# TPS54560_5V_optymalizacja.net
KiCad netlist of a schematic drawn in Altium Designer
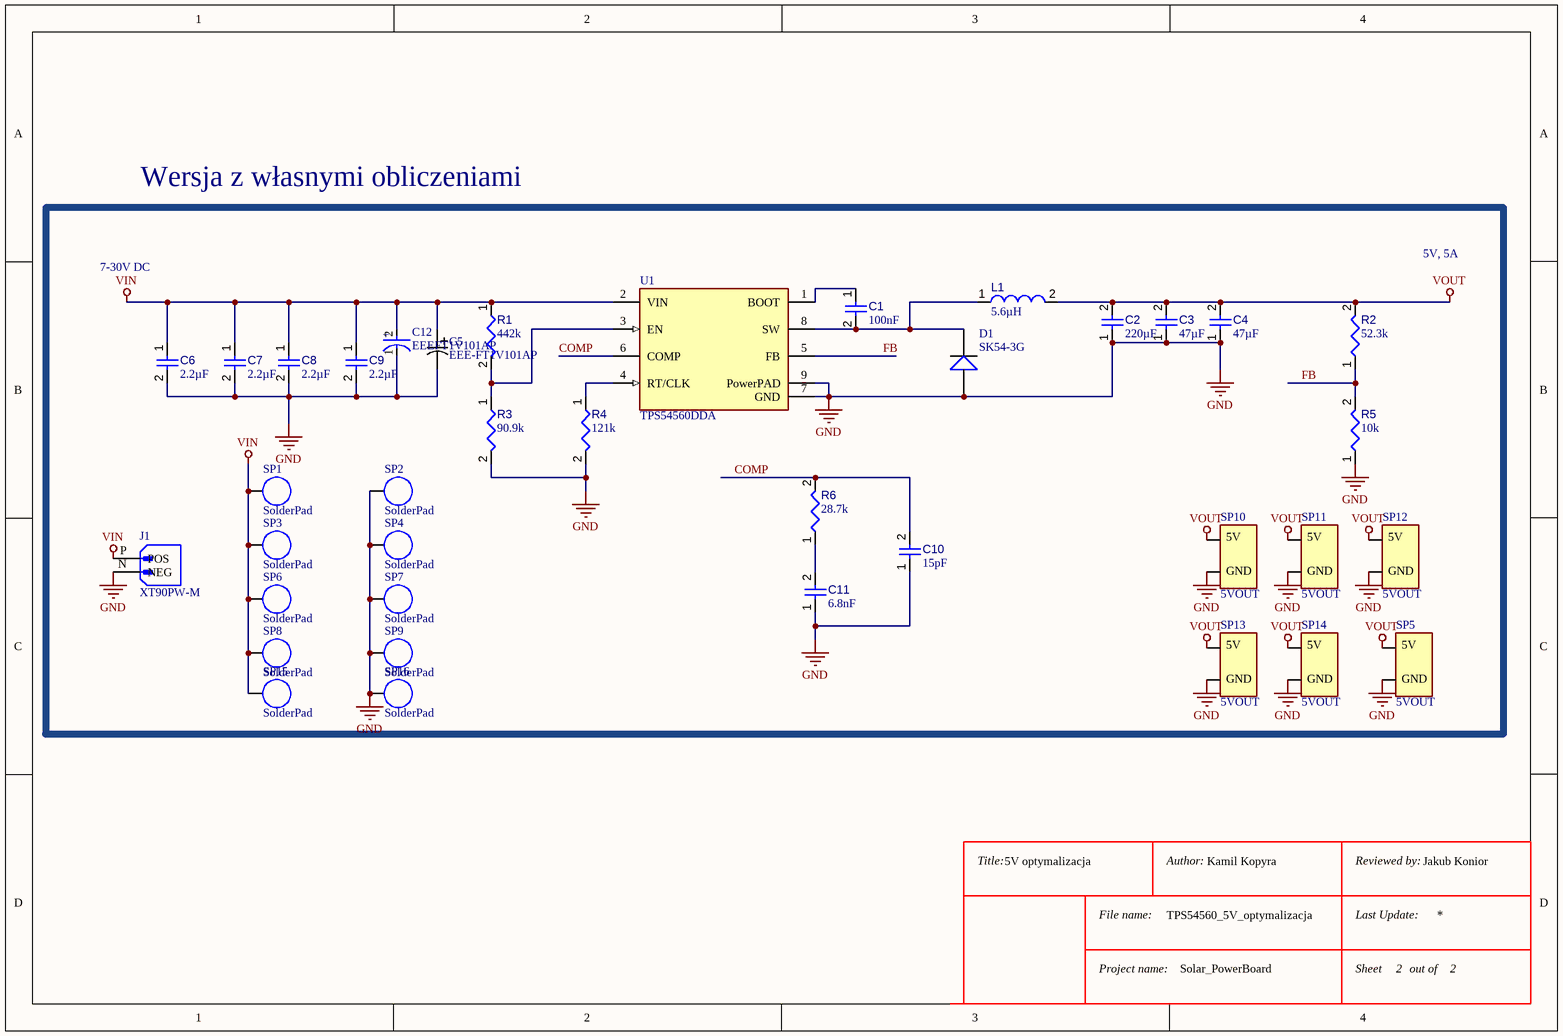
[diagram p0: TPS54560_5V_optymalizacja.SchDoc]

(export (version "E")
  (design (tool "Eeschema 10.0.6"))
  (components
    (comp (ref "C1")
      (value "100nF")
      (footprint "CAPC0805(2012)145_L")
      (description "Chip Capacitor, 100nF +/-40%, 6.3V, 0805, Thickness 1.45 mm")
      (fields (field (name "TOLERANCE") "10%") (field (name "Comment") "Capacitor 100nF +/-40% 6.3V 0805"))
      (libsource (lib "Solar_Plane_Jakub_Konior") (part "CAP-NP-2"))
    )
    (comp (ref "C2")
      (value "220µF")
      (footprint "CAPC3216X180X50NL20T25")
      (description "Chip Capacitor, 220 uF, +/- 10%, 16 V, 1206 (3216 Metric)")
      (fields (field (name "TOLERANCE") "10%") (field (name "Comment") "Capacitor 220 uF +/- 10% 16 V 1206"))
      (libsource (lib "Solar_Plane_Jakub_Konior") (part "CAP-NP-2"))
    )
    (comp (ref "C3")
      (value "47µF")
      (footprint "CAPC0805(2012)145_L")
      (description "Chip Capacitor, 47µF +/-40%, 6.3V, 0805, Thickness 1.45 mm")
      (fields (field (name "TOLERANCE") "10%") (field (name "Comment") "Capacitor 47µF +/-40% 6.3V 0805"))
      (libsource (lib "Solar_Plane_Jakub_Konior") (part "CAP-NP-2"))
    )
    (comp (ref "C4")
      (value "47µF")
      (footprint "CAPC0805(2012)145_L")
      (description "Chip Capacitor, 47µF +/-40%, 6.3V, 0805, Thickness 1.45 mm")
      (fields (field (name "TOLERANCE") "10%") (field (name "Comment") "Capacitor 47µF +/-40% 6.3V 0805"))
      (libsource (lib "Solar_Plane_Jakub_Konior") (part "CAP-NP-2"))
    )
    (comp (ref "C5")
      (value "EEE-FT1V101AP")
      (footprint "CapBulk")
      (description "Description")
      (fields (field (name "COPYRIGHT") "Copyright (C) 2025 Ultra Librarian. All rights reserved."))
      (libsource (lib "AltiumSymbolLibrary") (part "EEE-FT1V101AP"))
    )
    (comp (ref "C6")
      (value "2.2µF")
      (footprint "CAPC0805(2012)145_L")
      (description "Chip Capacitor, 2.2µF +/-40%, 35V, 0805, Thickness 1.45 mm")
      (fields (field (name "TOLERANCE") "20%") (field (name "Comment") "Capacitor 2.2µF +/-40% 35V 0805"))
      (libsource (lib "Solar_Plane_Jakub_Konior") (part "CAP-NP-2"))
    )
    (comp (ref "C7")
      (value "2.2µF")
      (footprint "CAPC0805(2012)145_L")
      (description "Chip Capacitor, 2.2µF +/-40%, 35V, 0805, Thickness 1.45 mm")
      (fields (field (name "TOLERANCE") "20%") (field (name "Comment") "Capacitor 2.2µF +/-40% 35V 0805"))
      (libsource (lib "Solar_Plane_Jakub_Konior") (part "CAP-NP-2"))
    )
    (comp (ref "C8")
      (value "2.2µF")
      (footprint "CAPC0805(2012)145_L")
      (description "Chip Capacitor, 2.2µF +/-40%, 35V, 0805, Thickness 1.45 mm")
      (fields (field (name "TOLERANCE") "20%") (field (name "Comment") "Capacitor 2.2µF +/-40% 35V 0805"))
      (libsource (lib "Solar_Plane_Jakub_Konior") (part "CAP-NP-2"))
    )
    (comp (ref "C9")
      (value "2.2µF")
      (footprint "CAPC0805(2012)145_L")
      (description "Chip Capacitor, 2.2µF +/-40%, 35V, 0805, Thickness 1.45 mm")
      (fields (field (name "TOLERANCE") "20%") (field (name "Comment") "Capacitor 2.2µF +/-40% 35V 0805"))
      (libsource (lib "Solar_Plane_Jakub_Konior") (part "CAP-NP-2"))
    )
    (comp (ref "C10")
      (value "15pF")
      (footprint "CAPC0402(1005)60_L")
      (description "Chip Capacitor, 15pF +/-20%, 10V, 0402, Thickness 0.6 mm")
      (fields (field (name "TOLERANCE") "20%") (field (name "Comment") "Capacitor 15pF +/-20% 10V 0402"))
      (libsource (lib "Solar_Plane_Jakub_Konior") (part "CAP-NP-2"))
    )
    (comp (ref "C11")
      (value "6.8nF")
      (footprint "CAPC0402(1005)60_L")
      (description "Chip Capacitor, 15pF +/-20%, 10V, 0402, Thickness 0.6 mm")
      (fields (field (name "TOLERANCE") "20%") (field (name "Comment") "Capacitor 15pF +/-20% 10V 0402"))
      (libsource (lib "Solar_Plane_Jakub_Konior") (part "CAP-NP-2"))
    )
    (comp (ref "C12")
      (value "EEEFT1V101AP")
      (footprint "FP-FTD-MFG")
      (description "CAP ALUM 100UF 20% 35V SMD")
      (fields (field (name "VOLTAGE") "35V") (field (name "TOLERANCE") "20%"))
      (libsource (lib "Altium Content Vault") (part "a00bbbee19879c290e62620ae7e47b1"))
    )
    (comp (ref "D1")
      (value "SK54-3G")
      (footprint "SK54-3G")
      (libsource (lib "AltiumSymbolLibrary") (part "Diode"))
    )
    (comp (ref "J1")
      (value "XT90PW-M")
      (footprint "AMASS_XT90PW-M")
      (description "Socket; DC supply; XT90; male; PIN: 2; on PCBs; THT; Colour: yellow")
      (fields (field (name "MF") "AMASS"))
      (libsource (lib "Solar_Plane_Jakub_Konior") (part "XT90PW-M"))
    )
    (comp (ref "L1")
      (value "5.6µH")
      (footprint "SUSUMU-PCMB063T_V")
      (description "Shielded Wirewound Inductor, 5.6 uH, +/- 20%, -20 to 120 degC, 2-Pin SMD, RoHS, Tape and Reel")
      (fields (field (name "TOLERANCE") "20%") (field (name "Comment") "Inductor 5.6uH"))
      (libsource (lib "Solar_Plane_Jakub_Konior") (part "CMP-001-0020-1"))
    )
    (comp (ref "R1")
      (value "442k")
      (footprint "RESC0805(2012)_L")
      (description "Chip Resistor, 442 kOhms, +/-5%, 125 mW, -55 to 155 degC, 0805")
      (fields (field (name "TOLERANCE") "5%") (field (name "POWER") "125mW"))
      (libsource (lib "Solar_Plane_Jakub_Konior") (part "RES-2"))
    )
    (comp (ref "R2")
      (value "52.3k")
      (footprint "RESC1005X40X25ML05T05")
      (description "Chip Resistor, 52.3 KOhm, +/- 1%, 0.1 W, -55 to 155 degC, 0402 (1005 Metric)")
      (fields (field (name "TOLERANCE") "1%") (field (name "POWER") "100mW"))
      (libsource (lib "Solar_Plane_Jakub_Konior") (part "RES-2"))
    )
    (comp (ref "R3")
      (value "90.9k")
      (footprint "RESC0805(2012)_L")
      (description "Chip Resistor, 90.9 kOhms, +/-5 %, 125 mW, -55 to 155 degC, 0805")
      (fields (field (name "TOLERANCE") "5%") (field (name "POWER") "125mW"))
      (libsource (lib "Solar_Plane_Jakub_Konior") (part "RES-2"))
    )
    (comp (ref "R4")
      (value "121k")
      (footprint "RESC0805(2012)_L")
      (description "Chip Resistor, 121 kOhms, +/-5 %, 125 mW, -55 to 155 degC, 0805")
      (fields (field (name "POWER") "125mW") (field (name "TOLERANCE") "5%"))
      (libsource (lib "Solar_Plane_Jakub_Konior") (part "RES-2"))
    )
    (comp (ref "R5")
      (value "10k")
      (footprint "RESC1005X40X25ML05T05")
      (description "Chip Resistor, 10 KOhm, +/- 1%, 0.1 W, -55 to 155 degC, 0402 (1005 Metric)")
      (fields (field (name "TOLERANCE") "1%") (field (name "POWER") "100mW"))
      (libsource (lib "Solar_Plane_Jakub_Konior") (part "RES-2"))
    )
    (comp (ref "R6")
      (value "28.7k")
      (footprint "RESC1005X40X25ML05T05")
      (description "Chip Resistor, 28.7 KOhm, +/- 1%, 0.1 W, -55 to 155 degC, 0402 (1005 Metric)")
      (fields (field (name "POWER") "100mW") (field (name "TOLERANCE") "1%"))
      (libsource (lib "Solar_Plane_Jakub_Konior") (part "RES-2"))
    )
    (comp (ref "SP1")
      (value "SolderPad")
      (footprint "SolderPad")
      (libsource (lib "AltiumSymbolLibrary") (part "SolderPad"))
    )
    (comp (ref "SP2")
      (value "SolderPad")
      (footprint "SolderPad")
      (libsource (lib "AltiumSymbolLibrary") (part "SolderPad"))
    )
    (comp (ref "SP3")
      (value "SolderPad")
      (footprint "SolderPad")
      (libsource (lib "AltiumSymbolLibrary") (part "SolderPad"))
    )
    (comp (ref "SP4")
      (value "SolderPad")
      (footprint "SolderPad")
      (libsource (lib "AltiumSymbolLibrary") (part "SolderPad"))
    )
    (comp (ref "SP5")
      (value "5VOUT")
      (footprint "5VOUT")
      (libsource (lib "AltiumSymbolLibrary") (part "5VOUT"))
    )
    (comp (ref "SP6")
      (value "SolderPad")
      (footprint "SolderPad")
      (libsource (lib "AltiumSymbolLibrary") (part "SolderPad"))
    )
    (comp (ref "SP7")
      (value "SolderPad")
      (footprint "SolderPad")
      (libsource (lib "AltiumSymbolLibrary") (part "SolderPad"))
    )
    (comp (ref "SP8")
      (value "SolderPad")
      (footprint "SolderPad")
      (libsource (lib "AltiumSymbolLibrary") (part "SolderPad"))
    )
    (comp (ref "SP9")
      (value "SolderPad")
      (footprint "SolderPad")
      (libsource (lib "AltiumSymbolLibrary") (part "SolderPad"))
    )
    (comp (ref "SP10")
      (value "5VOUT")
      (footprint "5VOUT")
      (libsource (lib "AltiumSymbolLibrary") (part "5VOUT"))
    )
    (comp (ref "SP11")
      (value "5VOUT")
      (footprint "5VOUT")
      (libsource (lib "AltiumSymbolLibrary") (part "5VOUT"))
    )
    (comp (ref "SP12")
      (value "5VOUT")
      (footprint "5VOUT")
      (libsource (lib "AltiumSymbolLibrary") (part "5VOUT"))
    )
    (comp (ref "SP13")
      (value "5VOUT")
      (footprint "5VOUT")
      (libsource (lib "AltiumSymbolLibrary") (part "5VOUT"))
    )
    (comp (ref "SP14")
      (value "5VOUT")
      (footprint "5VOUT")
      (libsource (lib "AltiumSymbolLibrary") (part "5VOUT"))
    )
    (comp (ref "SP15")
      (value "SolderPad")
      (footprint "SolderPad")
      (libsource (lib "AltiumSymbolLibrary") (part "SolderPad"))
    )
    (comp (ref "SP16")
      (value "SolderPad")
      (footprint "SolderPad")
      (libsource (lib "AltiumSymbolLibrary") (part "SolderPad"))
    )
    (comp (ref "U1")
      (value "TPS54560DDA")
      (footprint "FP-DDA0008E-MFG")
      (description "IC REG BCK SPLIT RAIL ADJ 8SOPWR")
      (fields
        (field (name "OCTOPART") "https://octopart.com/tps54560dda-texas+instruments-26977150")
        (field (name "MANUFACTURER") "Texas Instruments")
      )
      (libsource (lib "Altium Content Vault") (part "92fa32c5fb0b456cc3a934f0e7b6d8f"))
    )
  )
  (nets
    (net (code "1") (name "/COMP") (class "Default")
      (node (ref "C10") (pin "2") (pinfunction "2_2") (pintype "passive"))
      (node (ref "R6") (pin "2") (pinfunction "2_2") (pintype "passive"))
      (node (ref "U1") (pin "6") (pinfunction "COMP_6") (pintype "passive"))
    )
    (net (code "2") (name "/FB") (class "Default")
      (node (ref "R2") (pin "1") (pinfunction "1_1") (pintype "passive"))
      (node (ref "R5") (pin "2") (pinfunction "2_2") (pintype "passive"))
      (node (ref "U1") (pin "5") (pinfunction "FB_5") (pintype "passive"))
    )
    (net (code "3") (name "GND") (class "Default")
      (node (ref "C10") (pin "1") (pinfunction "1_1") (pintype "passive"))
      (node (ref "C11") (pin "1") (pinfunction "1_1") (pintype "passive"))
      (node (ref "C12") (pin "1") (pinfunction "C_1") (pintype "passive"))
      (node (ref "C2") (pin "1") (pinfunction "1_1") (pintype "passive"))
      (node (ref "C3") (pin "1") (pinfunction "1_1") (pintype "passive"))
      (node (ref "C4") (pin "1") (pinfunction "1_1") (pintype "passive"))
      (node (ref "C5") (pin "2") (pinfunction "2_2") (pintype "passive"))
      (node (ref "C6") (pin "2") (pinfunction "2_2") (pintype "passive"))
      (node (ref "C7") (pin "2") (pinfunction "2_2") (pintype "passive"))
      (node (ref "C8") (pin "2") (pinfunction "2_2") (pintype "passive"))
      (node (ref "C9") (pin "2") (pinfunction "2_2") (pintype "passive"))
      (node (ref "D1") (pin "1") (pintype "passive"))
      (node (ref "J1") (pin "N") (pinfunction "NEG_N") (pintype "passive"))
      (node (ref "R3") (pin "2") (pinfunction "2_2") (pintype "passive"))
      (node (ref "R4") (pin "2") (pinfunction "2_2") (pintype "passive"))
      (node (ref "R5") (pin "1") (pinfunction "1_1") (pintype "passive"))
      (node (ref "SP10") (pin "2") (pintype "passive"))
      (node (ref "SP11") (pin "2") (pintype "passive"))
      (node (ref "SP12") (pin "2") (pintype "passive"))
      (node (ref "SP13") (pin "2") (pintype "passive"))
      (node (ref "SP14") (pin "2") (pintype "passive"))
      (node (ref "SP16") (pin "1") (pintype "passive"))
      (node (ref "SP2") (pin "1") (pintype "passive"))
      (node (ref "SP4") (pin "1") (pintype "passive"))
      (node (ref "SP5") (pin "2") (pintype "passive"))
      (node (ref "SP7") (pin "1") (pintype "passive"))
      (node (ref "SP9") (pin "1") (pintype "passive"))
      (node (ref "U1") (pin "7") (pinfunction "GND_7") (pintype "power_in"))
      (node (ref "U1") (pin "9") (pinfunction "PowerPAD_9") (pintype "power_in"))
    )
    (net (code "4") (name "Net-(C11-Pad2)") (class "Default")
      (node (ref "C11") (pin "2") (pinfunction "2_2") (pintype "passive"))
      (node (ref "R6") (pin "1") (pinfunction "1_1") (pintype "passive"))
    )
    (net (code "5") (name "Net-(U1-BOOT)") (class "Default")
      (node (ref "C1") (pin "1") (pinfunction "1_1") (pintype "passive"))
      (node (ref "U1") (pin "1") (pinfunction "BOOT_1") (pintype "passive"))
    )
    (net (code "6") (name "Net-(U1-EN)") (class "Default")
      (node (ref "R1") (pin "2") (pinfunction "2_2") (pintype "passive"))
      (node (ref "R3") (pin "1") (pinfunction "1_1") (pintype "passive"))
      (node (ref "U1") (pin "3") (pinfunction "EN_3") (pintype "input"))
    )
    (net (code "7") (name "Net-(U1-RT{slash}CLK)") (class "Default")
      (node (ref "R4") (pin "1") (pinfunction "1_1") (pintype "passive"))
      (node (ref "U1") (pin "4") (pinfunction "RT/CLK_4") (pintype "input"))
    )
    (net (code "8") (name "Net-(U1-SW)") (class "Default")
      (node (ref "C1") (pin "2") (pinfunction "2_2") (pintype "passive"))
      (node (ref "D1") (pin "2") (pintype "passive"))
      (node (ref "L1") (pin "1") (pinfunction "1_1") (pintype "passive"))
      (node (ref "U1") (pin "8") (pinfunction "SW_8") (pintype "passive"))
    )
    (net (code "9") (name "VIN") (class "Default")
      (node (ref "C12") (pin "2") (pinfunction "A_2") (pintype "passive"))
      (node (ref "C5") (pin "1") (pinfunction "1_1") (pintype "passive"))
      (node (ref "C6") (pin "1") (pinfunction "1_1") (pintype "passive"))
      (node (ref "C7") (pin "1") (pinfunction "1_1") (pintype "passive"))
      (node (ref "C8") (pin "1") (pinfunction "1_1") (pintype "passive"))
      (node (ref "C9") (pin "1") (pinfunction "1_1") (pintype "passive"))
      (node (ref "J1") (pin "P") (pinfunction "POS_P") (pintype "passive"))
      (node (ref "R1") (pin "1") (pinfunction "1_1") (pintype "passive"))
      (node (ref "SP1") (pin "1") (pintype "passive"))
      (node (ref "SP15") (pin "1") (pintype "passive"))
      (node (ref "SP3") (pin "1") (pintype "passive"))
      (node (ref "SP6") (pin "1") (pintype "passive"))
      (node (ref "SP8") (pin "1") (pintype "passive"))
      (node (ref "U1") (pin "2") (pinfunction "VIN_2") (pintype "power_in"))
    )
    (net (code "10") (name "VOUT") (class "Default")
      (node (ref "C2") (pin "2") (pinfunction "2_2") (pintype "passive"))
      (node (ref "C3") (pin "2") (pinfunction "2_2") (pintype "passive"))
      (node (ref "C4") (pin "2") (pinfunction "2_2") (pintype "passive"))
      (node (ref "L1") (pin "2") (pinfunction "2_2") (pintype "passive"))
      (node (ref "R2") (pin "2") (pinfunction "2_2") (pintype "passive"))
      (node (ref "SP10") (pin "1") (pintype "passive"))
      (node (ref "SP11") (pin "1") (pintype "passive"))
      (node (ref "SP12") (pin "1") (pintype "passive"))
      (node (ref "SP13") (pin "1") (pintype "passive"))
      (node (ref "SP14") (pin "1") (pintype "passive"))
      (node (ref "SP5") (pin "1") (pintype "passive"))
    )
  )
)
